# Y-babies_ATtiny84.net
KiCad netlist of a schematic drawn in EAGLE
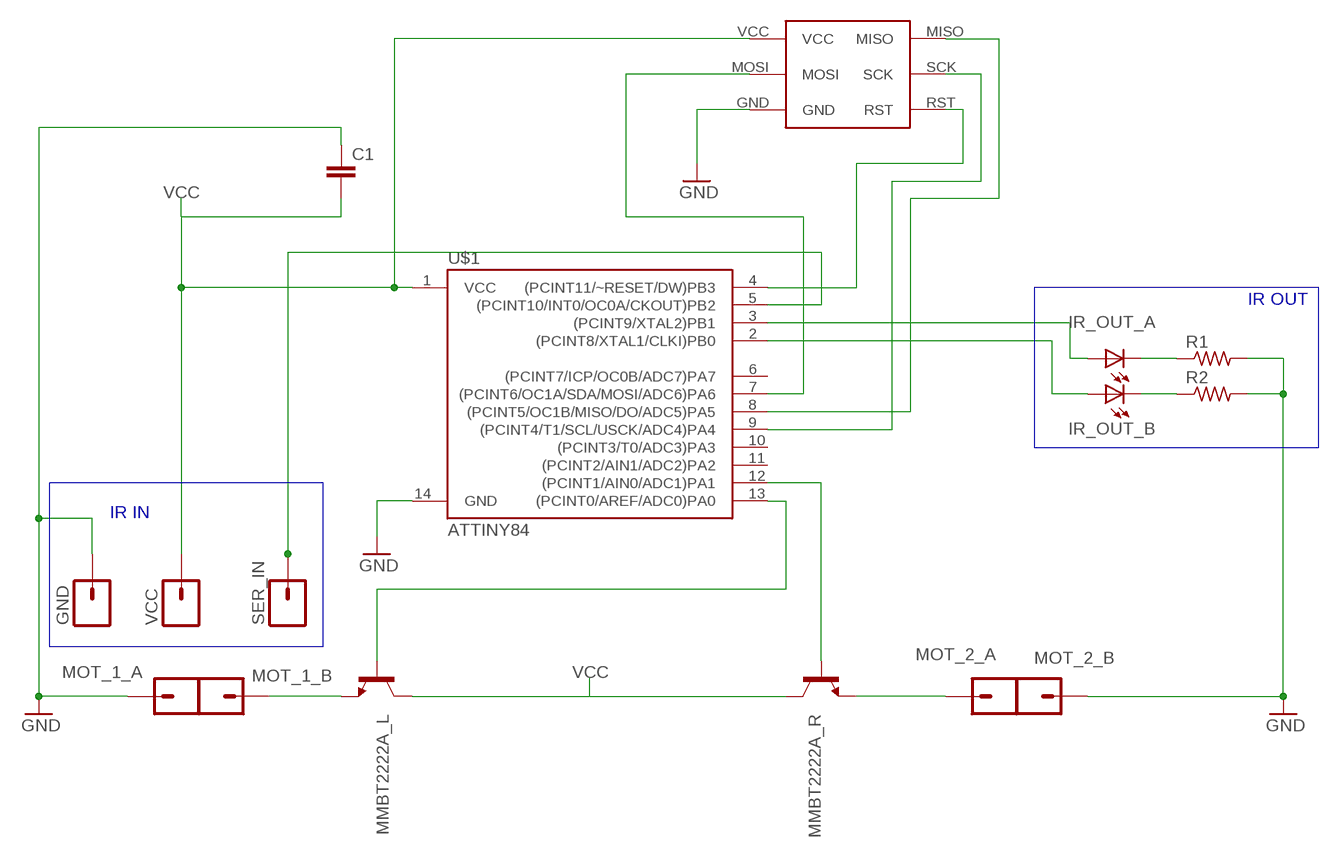
[diagram p0: schematic, sheet 1]

(export (version "E")
  (design (tool "Eeschema 10.0.6"))
  (components
    (comp (ref "C1")
      (value "CAPSMD")
      (footprint "eagle-import:GRM43D")
      (libsource (lib "eagle-import") (part "CAPSMD"))
    )
    (comp (ref "GND")
      (value "M01PTH")
      (footprint "eagle-import:1X01")
      (libsource (lib "eagle-import") (part "M01PTH"))
    )
    (comp (ref "IR_OUT_A")
      (value "LED3MM")
      (footprint "eagle-import:LED3MM")
      (libsource (lib "eagle-import") (part "LED3MM"))
    )
    (comp (ref "IR_OUT_B")
      (value "LED3MM")
      (footprint "eagle-import:LED3MM")
      (libsource (lib "eagle-import") (part "LED3MM"))
    )
    (comp (ref "MMBT2222A_L")
      (value "TRANSISTOR_NPNSOT23")
      (footprint "eagle-import:SOT23")
      (libsource (lib "eagle-import") (part "TRANSISTOR_NPNSOT23"))
    )
    (comp (ref "MMBT2222A_R")
      (value "TRANSISTOR_NPNSOT23")
      (footprint "eagle-import:SOT23")
      (libsource (lib "eagle-import") (part "TRANSISTOR_NPNSOT23"))
    )
    (comp (ref "MOT_1_A")
      (value "M01SMD-4.5X1.5")
      (footprint "eagle-import:PAD-1.5X4.5")
      (libsource (lib "eagle-import") (part "M01SMD-4.5X1.5"))
    )
    (comp (ref "MOT_1_B")
      (value "M01SMD-4.5X1.5")
      (footprint "eagle-import:PAD-1.5X4.5")
      (libsource (lib "eagle-import") (part "M01SMD-4.5X1.5"))
    )
    (comp (ref "MOT_2_A")
      (value "M01SMD-4.5X1.5")
      (footprint "eagle-import:PAD-1.5X4.5")
      (libsource (lib "eagle-import") (part "M01SMD-4.5X1.5"))
    )
    (comp (ref "MOT_2_B")
      (value "M01SMD-4.5X1.5")
      (footprint "eagle-import:PAD-1.5X4.5")
      (libsource (lib "eagle-import") (part "M01SMD-4.5X1.5"))
    )
    (comp (ref "R1")
      (value "R-US_R0805W")
      (footprint "eagle-import:R0805W")
      (libsource (lib "eagle-import") (part "R-US_R0805W"))
    )
    (comp (ref "R2")
      (value "R-US_R0805W")
      (footprint "eagle-import:R0805W")
      (libsource (lib "eagle-import") (part "R-US_R0805W"))
    )
    (comp (ref "SER_IN")
      (value "M01PTH")
      (footprint "eagle-import:1X01")
      (libsource (lib "eagle-import") (part "M01PTH"))
    )
    (comp (ref "U$1")
      (value "ATTINY84")
      (footprint "eagle-import:SO14")
      (libsource (lib "eagle-import") (part "ATTINY84"))
    )
    (comp (ref "U$2")
      (value "POGO_PIN_SPI_PAD")
      (footprint "eagle-import:POGO_PIN_SPI_PAD")
      (libsource (lib "eagle-import") (part "POGO_PIN_SPI_PAD"))
    )
    (comp (ref "VCC")
      (value "M01PTH")
      (footprint "eagle-import:1X01")
      (libsource (lib "eagle-import") (part "M01PTH"))
    )
  )
  (nets
    (net (code "1") (name "/VCC") (class "Default")
      (node (ref "C1") (pin "C") (pinfunction "2_C") (pintype "passive"))
      (node (ref "MMBT2222A_L") (pin "3") (pinfunction "C_3") (pintype "passive"))
      (node (ref "MMBT2222A_R") (pin "3") (pinfunction "C_3") (pintype "passive"))
      (node (ref "U$1") (pin "1") (pinfunction "VCC_1") (pintype "bidirectional"))
      (node (ref "U$2") (pin "VCC") (pinfunction "VCC_VCC") (pintype "bidirectional"))
      (node (ref "VCC") (pin "1") (pinfunction "1_1") (pintype "passive"))
    )
    (net (code "2") (name "GND") (class "Default")
      (node (ref "C1") (pin "A") (pinfunction "1_A") (pintype "passive"))
      (node (ref "GND") (pin "1") (pinfunction "1_1") (pintype "passive"))
      (node (ref "MOT_1_A") (pin "P$1") (pinfunction "1_P$1") (pintype "passive"))
      (node (ref "MOT_2_B") (pin "P$1") (pinfunction "1_P$1") (pintype "passive"))
      (node (ref "R1") (pin "2") (pinfunction "2_2") (pintype "passive"))
      (node (ref "R2") (pin "2") (pinfunction "2_2") (pintype "passive"))
      (node (ref "U$1") (pin "14") (pinfunction "GND_14") (pintype "bidirectional"))
      (node (ref "U$2") (pin "GND") (pinfunction "GND_GND") (pintype "bidirectional"))
    )
    (net (code "3") (name "Net-(IR_OUT_A-C)") (class "Default")
      (node (ref "IR_OUT_A") (pin "K") (pinfunction "C_K") (pintype "passive"))
      (node (ref "R1") (pin "1") (pinfunction "1_1") (pintype "passive"))
    )
    (net (code "4") (name "Net-(IR_OUT_B-C)") (class "Default")
      (node (ref "IR_OUT_B") (pin "K") (pinfunction "C_K") (pintype "passive"))
      (node (ref "R2") (pin "1") (pinfunction "1_1") (pintype "passive"))
    )
    (net (code "5") (name "Net-(MMBT2222A_L-B)") (class "Default")
      (node (ref "MMBT2222A_L") (pin "1") (pinfunction "B_1") (pintype "passive"))
      (node (ref "U$1") (pin "13") (pinfunction "(PCINT0/AREF/ADC0)PA0_13") (pintype "bidirectional"))
    )
    (net (code "6") (name "Net-(MMBT2222A_L-E)") (class "Default")
      (node (ref "MMBT2222A_L") (pin "2") (pinfunction "E_2") (pintype "passive"))
      (node (ref "MOT_1_B") (pin "P$1") (pinfunction "1_P$1") (pintype "passive"))
    )
    (net (code "7") (name "Net-(MMBT2222A_R-B)") (class "Default")
      (node (ref "MMBT2222A_R") (pin "1") (pinfunction "B_1") (pintype "passive"))
      (node (ref "U$1") (pin "12") (pinfunction "(PCINT1/AIN0/ADC1)PA1_12") (pintype "bidirectional"))
    )
    (net (code "8") (name "Net-(MMBT2222A_R-E)") (class "Default")
      (node (ref "MMBT2222A_R") (pin "2") (pinfunction "E_2") (pintype "passive"))
      (node (ref "MOT_2_A") (pin "P$1") (pinfunction "1_P$1") (pintype "passive"))
    )
    (net (code "9") (name "Net-(U$1-(PCINT4{slash}T1{slash}SCL{slash}USCK{slash}ADC4)PA4)") (class "Default")
      (node (ref "U$1") (pin "9") (pinfunction "(PCINT4/T1/SCL/USCK/ADC4)PA4_9") (pintype "bidirectional"))
      (node (ref "U$2") (pin "SCK") (pinfunction "SCK_SCK") (pintype "bidirectional"))
    )
    (net (code "10") (name "Net-(U$1-(PCINT5{slash}OC1B{slash}MISO{slash}DO{slash}ADC5)PA5)") (class "Default")
      (node (ref "U$1") (pin "8") (pinfunction "(PCINT5/OC1B/MISO/DO/ADC5)PA5_8") (pintype "bidirectional"))
      (node (ref "U$2") (pin "MISO") (pinfunction "MISO_MISO") (pintype "bidirectional"))
    )
    (net (code "11") (name "Net-(U$1-(PCINT6{slash}OC1A{slash}SDA{slash}MOSI{slash}ADC6)PA6)") (class "Default")
      (node (ref "U$1") (pin "7") (pinfunction "(PCINT6/OC1A/SDA/MOSI/ADC6)PA6_7") (pintype "bidirectional"))
      (node (ref "U$2") (pin "MOSI") (pinfunction "MOSI_MOSI") (pintype "bidirectional"))
    )
    (net (code "12") (name "Net-(U$1-(PCINT8{slash}XTAL1{slash}CLKI)PB0)") (class "Default")
      (node (ref "IR_OUT_B") (pin "A") (pinfunction "A_A") (pintype "passive"))
      (node (ref "U$1") (pin "2") (pinfunction "(PCINT8/XTAL1/CLKI)PB0_2") (pintype "bidirectional"))
    )
    (net (code "13") (name "Net-(U$1-(PCINT9{slash}XTAL2)PB1)") (class "Default")
      (node (ref "IR_OUT_A") (pin "A") (pinfunction "A_A") (pintype "passive"))
      (node (ref "U$1") (pin "3") (pinfunction "(PCINT9/XTAL2)PB1_3") (pintype "bidirectional"))
    )
    (net (code "14") (name "Net-(U$1-(PCINT10{slash}INT0{slash}OC0A{slash}CKOUT)PB2)") (class "Default")
      (node (ref "SER_IN") (pin "1") (pinfunction "1_1") (pintype "passive"))
      (node (ref "U$1") (pin "5") (pinfunction "(PCINT10/INT0/OC0A/CKOUT)PB2_5") (pintype "bidirectional"))
    )
    (net (code "15") (name "Net-(U$1-(PCINT11{slash}~{RESET{slash}DW})PB3)") (class "Default")
      (node (ref "U$1") (pin "4") (pinfunction "(PCINT11/~{RESET/DW})PB3_4") (pintype "bidirectional"))
      (node (ref "U$2") (pin "RST") (pinfunction "RST_RST") (pintype "bidirectional"))
    )
    (net (code "16") (name "unconnected-(U$1-(PCINT2{slash}AIN1{slash}ADC2)PA2-Pad11)") (class "Default")
      (node (ref "U$1") (pin "11") (pinfunction "(PCINT2/AIN1/ADC2)PA2_11") (pintype "bidirectional"))
    )
    (net (code "17") (name "unconnected-(U$1-(PCINT3{slash}T0{slash}ADC3)PA3-Pad10)") (class "Default")
      (node (ref "U$1") (pin "10") (pinfunction "(PCINT3/T0/ADC3)PA3_10") (pintype "bidirectional"))
    )
    (net (code "18") (name "unconnected-(U$1-(PCINT7{slash}ICP{slash}OC0B{slash}ADC7)PA7-Pad6)") (class "Default")
      (node (ref "U$1") (pin "6") (pinfunction "(PCINT7/ICP/OC0B/ADC7)PA7_6") (pintype "bidirectional"))
    )
  )
)
